# ShiftRegV1_3.net
KiCad netlist of a schematic drawn in EasyEDA
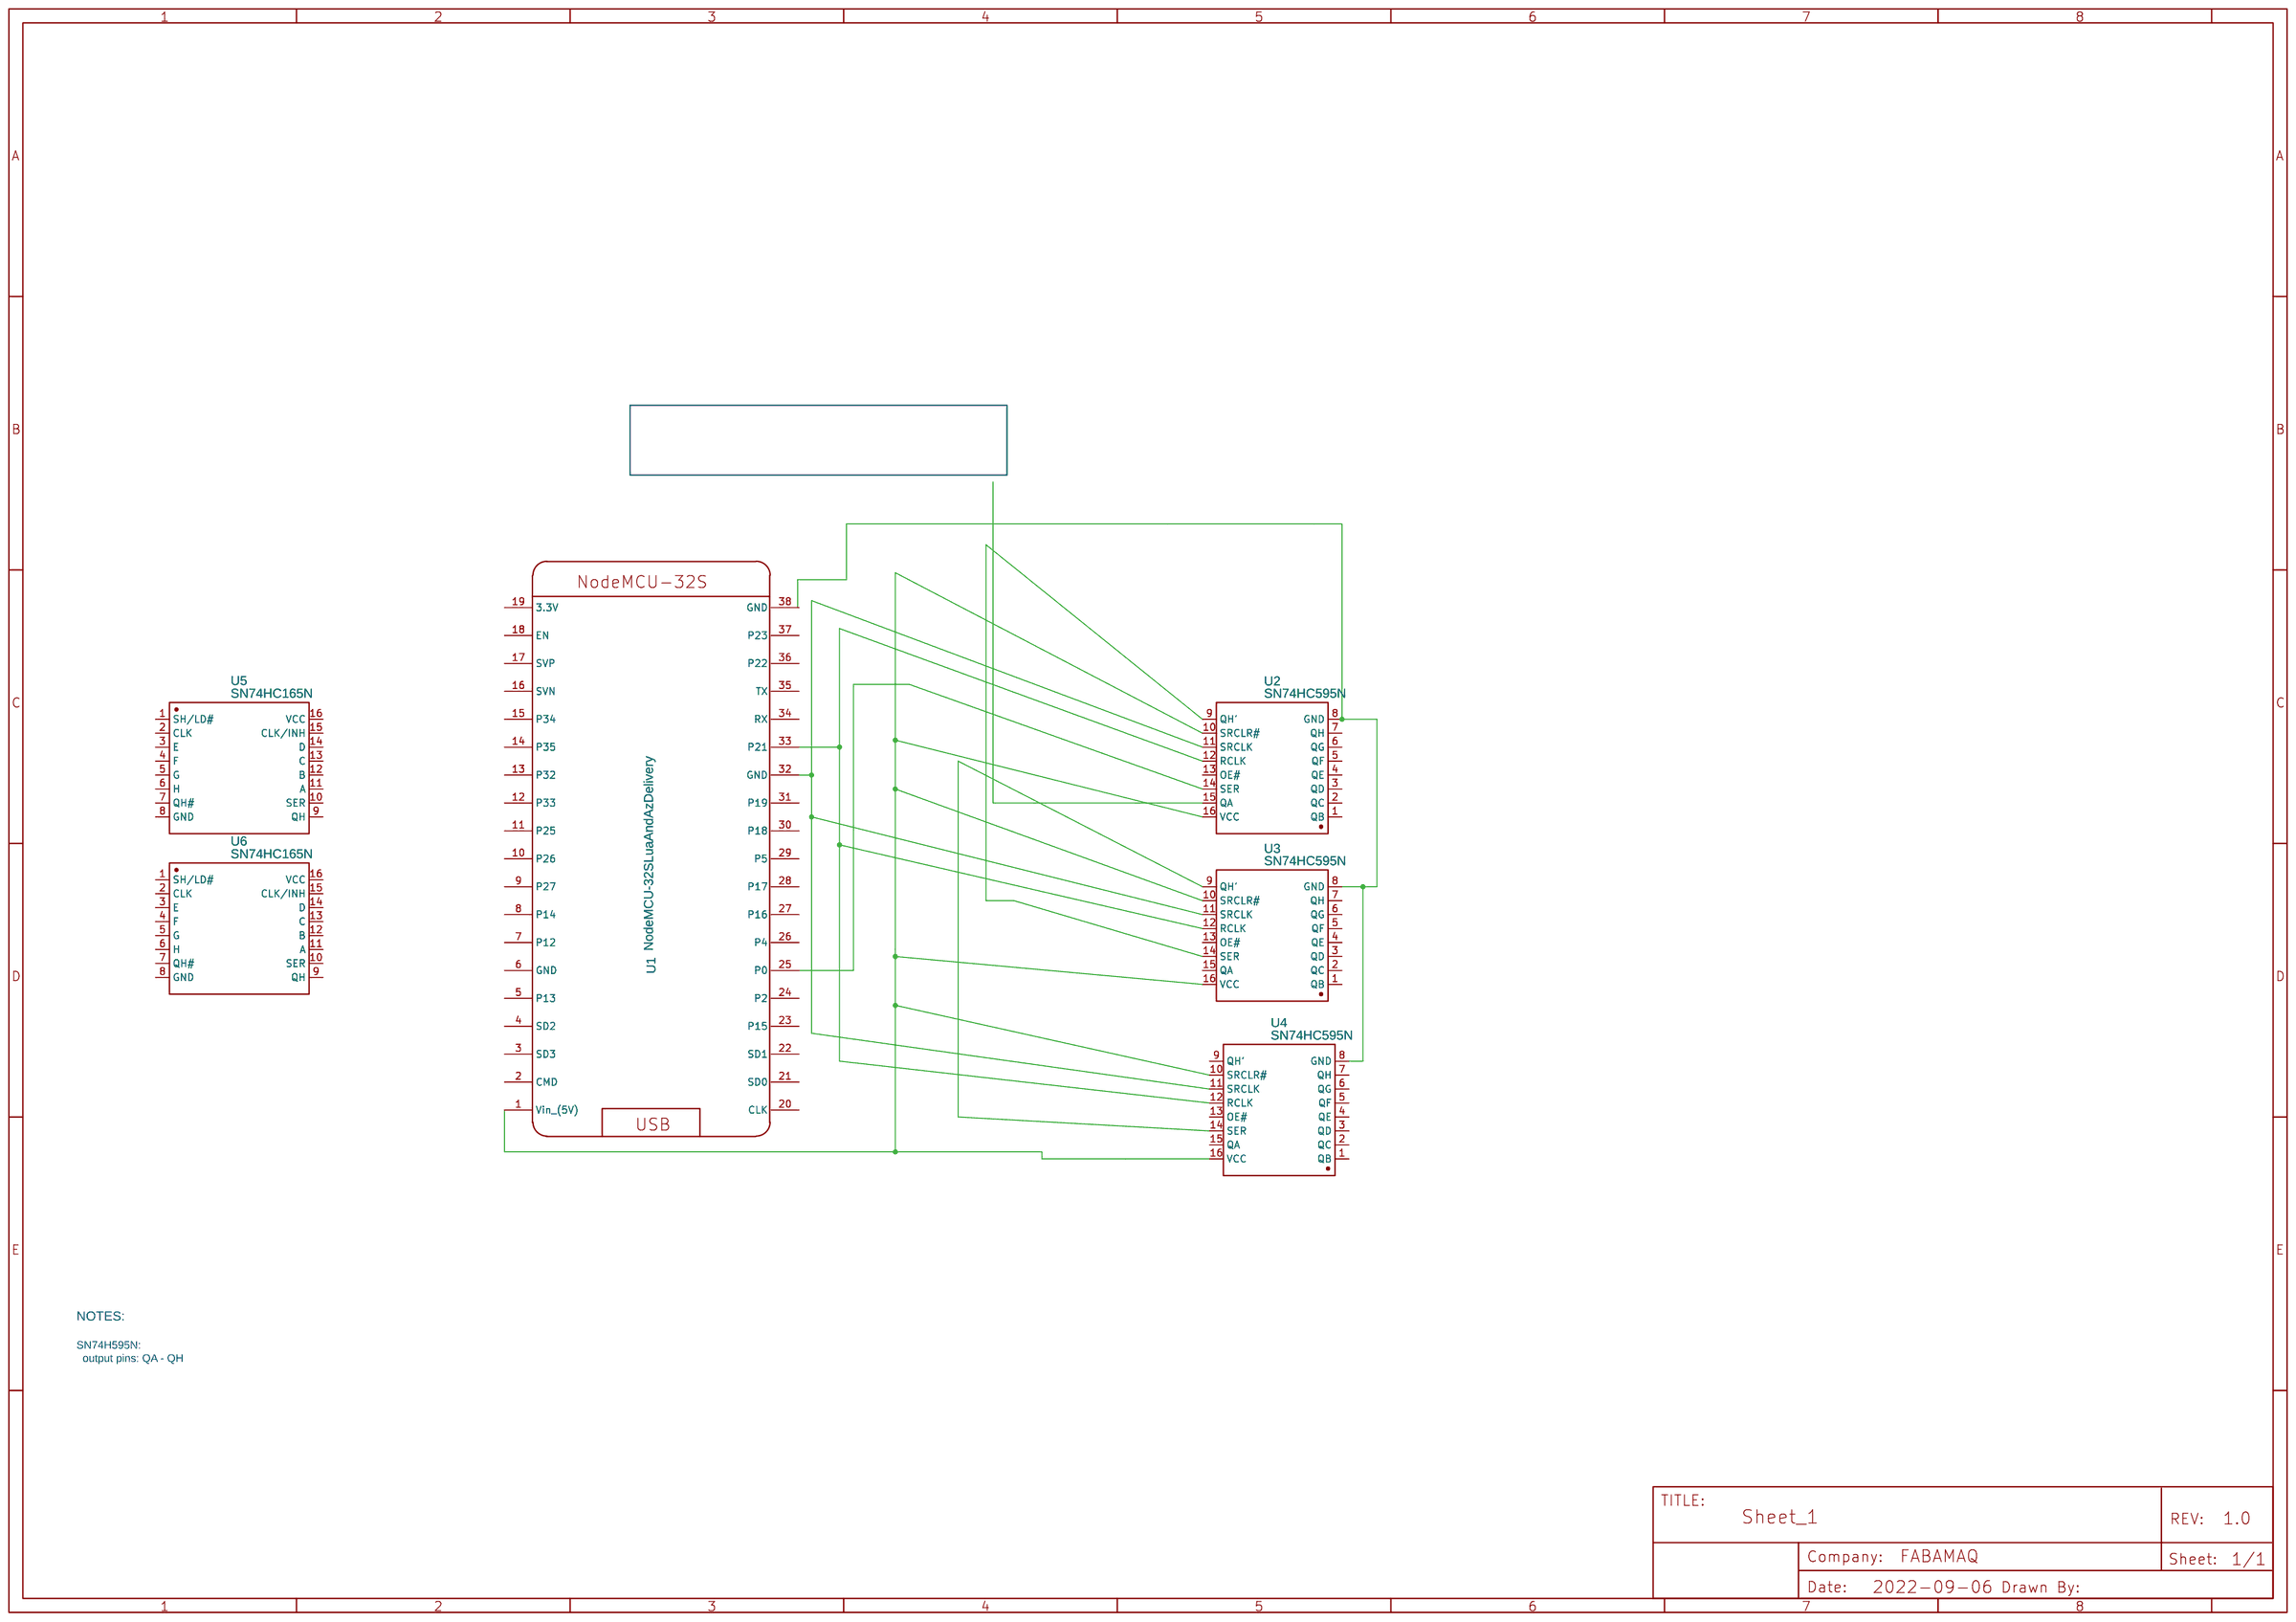
[diagram p0: Sheet_2]
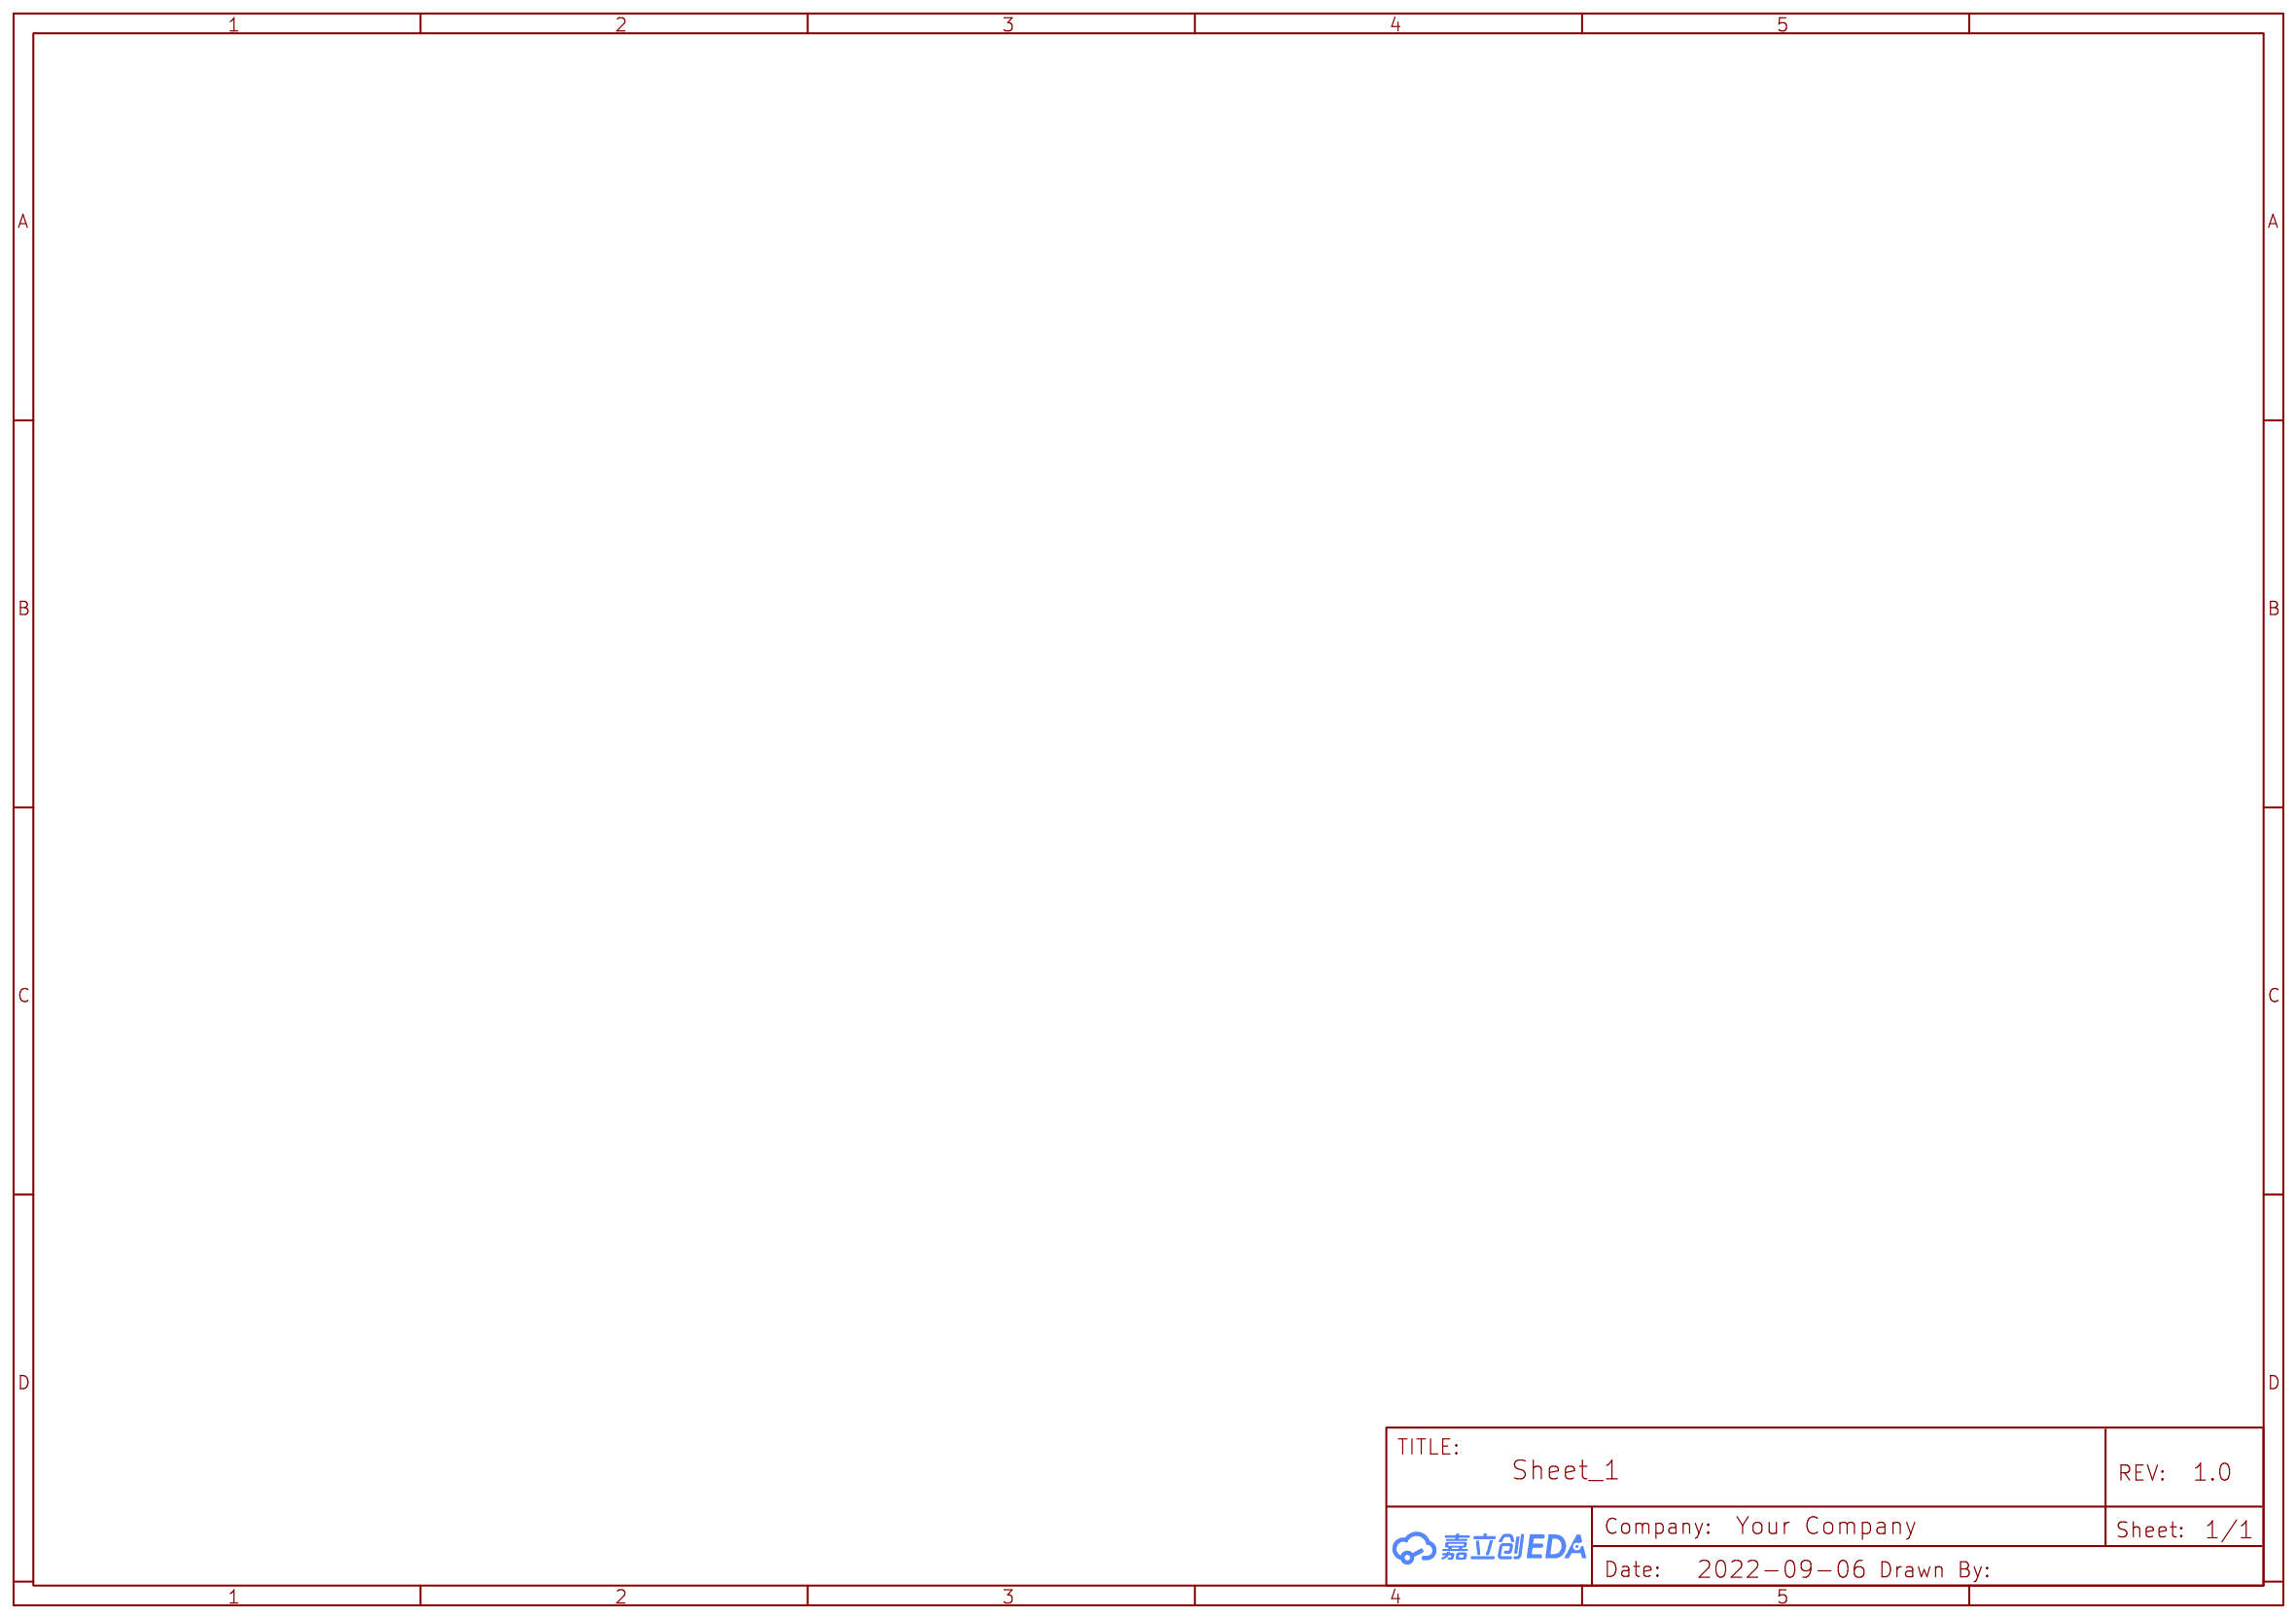
[diagram p1: Sheet_1]

(export (version "E")
  (design (tool "Eeschema 10.0.6"))
  (components
    (comp (ref "U1")
      (value "NodeMCU-32SLuaAndAzDelivery")
      (fields
        (field (name "BOM_Manufacturer Part") "NodeMCU-32SLua")
        (field (name "BOM_Supplier Part") "C111436")
      )
      (libsource (lib "") (part "NodeMCU-32SLuaAndAzDelivery"))
    )
    (comp (ref "U2")
      (value "SN74HC595N")
      (fields (field (name "BOM_Supplier Part") "C78711"))
      (libsource (lib "") (part "SN74HC595N"))
    )
    (comp (ref "U3")
      (value "SN74HC595N")
      (fields (field (name "BOM_Supplier Part") "C78711"))
      (libsource (lib "") (part "SN74HC595N"))
    )
    (comp (ref "U4")
      (value "SN74HC595N")
      (fields (field (name "BOM_Supplier Part") "C78711"))
      (libsource (lib "") (part "SN74HC595N"))
    )
    (comp (ref "U5")
      (value "SN74HC165N")
      (fields (field (name "BOM_Supplier Part") "C2909"))
      (libsource (lib "") (part "SN74HC165N"))
    )
    (comp (ref "U6")
      (value "SN74HC165N")
      (fields (field (name "BOM_Supplier Part") "C2909"))
      (libsource (lib "") (part "SN74HC165N"))
    )
  )
  (nets
    (net (code "1") (name "Net-(U1-P0)") (class "Default")
      (node (ref "U1") (pin "25") (pinfunction "P0_25") (pintype "unspecified"))
      (node (ref "U2") (pin "14") (pinfunction "SER_14") (pintype "unspecified"))
    )
    (net (code "2") (name "Net-(U1-P21)") (class "Default")
      (node (ref "U1") (pin "33") (pinfunction "P21_33") (pintype "unspecified"))
      (node (ref "U2") (pin "12") (pinfunction "RCLK_12") (pintype "unspecified"))
      (node (ref "U3") (pin "12") (pinfunction "RCLK_12") (pintype "unspecified"))
      (node (ref "U4") (pin "12") (pinfunction "RCLK_12") (pintype "unspecified"))
    )
    (net (code "3") (name "Net-(U1-Vin_(5V))") (class "Default")
      (node (ref "U1") (pin "1") (pinfunction "Vin_(5V)_1") (pintype "unspecified"))
      (node (ref "U2") (pin "10") (pinfunction "SRCLR#_10") (pintype "unspecified"))
      (node (ref "U2") (pin "16") (pinfunction "VCC_16") (pintype "unspecified"))
      (node (ref "U3") (pin "10") (pinfunction "SRCLR#_10") (pintype "unspecified"))
      (node (ref "U3") (pin "16") (pinfunction "VCC_16") (pintype "unspecified"))
      (node (ref "U4") (pin "10") (pinfunction "SRCLR#_10") (pintype "unspecified"))
      (node (ref "U4") (pin "16") (pinfunction "VCC_16") (pintype "unspecified"))
    )
    (net (code "4") (name "Net-(U2-GND)") (class "Default")
      (node (ref "U1") (pin "38") (pinfunction "GND_38") (pintype "unspecified"))
      (node (ref "U2") (pin "8") (pinfunction "GND_8") (pintype "unspecified"))
      (node (ref "U3") (pin "8") (pinfunction "GND_8") (pintype "unspecified"))
      (node (ref "U4") (pin "8") (pinfunction "GND_8") (pintype "unspecified"))
    )
    (net (code "5") (name "Net-(U2-QH')") (class "Default")
      (node (ref "U2") (pin "9") (pinfunction "QH'_9") (pintype "unspecified"))
      (node (ref "U3") (pin "14") (pinfunction "SER_14") (pintype "unspecified"))
    )
    (net (code "6") (name "Net-(U2-SRCLK)") (class "Default")
      (node (ref "U1") (pin "32") (pinfunction "GND_32") (pintype "unspecified"))
      (node (ref "U2") (pin "11") (pinfunction "SRCLK_11") (pintype "unspecified"))
      (node (ref "U3") (pin "11") (pinfunction "SRCLK_11") (pintype "unspecified"))
      (node (ref "U4") (pin "11") (pinfunction "SRCLK_11") (pintype "unspecified"))
    )
    (net (code "7") (name "Net-(U3-QH')") (class "Default")
      (node (ref "U3") (pin "9") (pinfunction "QH'_9") (pintype "unspecified"))
      (node (ref "U4") (pin "14") (pinfunction "SER_14") (pintype "unspecified"))
    )
    (net (code "8") (name "unconnected-(U1-3.3V-Pad19)") (class "Default")
      (node (ref "U1") (pin "19") (pinfunction "3.3V_19") (pintype "unspecified"))
    )
    (net (code "9") (name "unconnected-(U1-CLK-Pad20)") (class "Default")
      (node (ref "U1") (pin "20") (pinfunction "CLK_20") (pintype "unspecified"))
    )
    (net (code "10") (name "unconnected-(U1-CMD-Pad2)") (class "Default")
      (node (ref "U1") (pin "2") (pinfunction "CMD_2") (pintype "unspecified"))
    )
    (net (code "11") (name "unconnected-(U1-EN-Pad18)") (class "Default")
      (node (ref "U1") (pin "18") (pinfunction "EN_18") (pintype "unspecified"))
    )
    (net (code "12") (name "unconnected-(U1-GND-Pad6)") (class "Default")
      (node (ref "U1") (pin "6") (pinfunction "GND_6") (pintype "unspecified"))
    )
    (net (code "13") (name "unconnected-(U1-P2-Pad24)") (class "Default")
      (node (ref "U1") (pin "24") (pinfunction "P2_24") (pintype "unspecified"))
    )
    (net (code "14") (name "unconnected-(U1-P4-Pad26)") (class "Default")
      (node (ref "U1") (pin "26") (pinfunction "P4_26") (pintype "unspecified"))
    )
    (net (code "15") (name "unconnected-(U1-P5-Pad29)") (class "Default")
      (node (ref "U1") (pin "29") (pinfunction "P5_29") (pintype "unspecified"))
    )
    (net (code "16") (name "unconnected-(U1-P12-Pad7)") (class "Default")
      (node (ref "U1") (pin "7") (pinfunction "P12_7") (pintype "unspecified"))
    )
    (net (code "17") (name "unconnected-(U1-P13-Pad5)") (class "Default")
      (node (ref "U1") (pin "5") (pinfunction "P13_5") (pintype "unspecified"))
    )
    (net (code "18") (name "unconnected-(U1-P14-Pad8)") (class "Default")
      (node (ref "U1") (pin "8") (pinfunction "P14_8") (pintype "unspecified"))
    )
    (net (code "19") (name "unconnected-(U1-P15-Pad23)") (class "Default")
      (node (ref "U1") (pin "23") (pinfunction "P15_23") (pintype "unspecified"))
    )
    (net (code "20") (name "unconnected-(U1-P16-Pad27)") (class "Default")
      (node (ref "U1") (pin "27") (pinfunction "P16_27") (pintype "unspecified"))
    )
    (net (code "21") (name "unconnected-(U1-P17-Pad28)") (class "Default")
      (node (ref "U1") (pin "28") (pinfunction "P17_28") (pintype "unspecified"))
    )
    (net (code "22") (name "unconnected-(U1-P18-Pad30)") (class "Default")
      (node (ref "U1") (pin "30") (pinfunction "P18_30") (pintype "unspecified"))
    )
    (net (code "23") (name "unconnected-(U1-P19-Pad31)") (class "Default")
      (node (ref "U1") (pin "31") (pinfunction "P19_31") (pintype "unspecified"))
    )
    (net (code "24") (name "unconnected-(U1-P22-Pad36)") (class "Default")
      (node (ref "U1") (pin "36") (pinfunction "P22_36") (pintype "unspecified"))
    )
    (net (code "25") (name "unconnected-(U1-P23-Pad37)") (class "Default")
      (node (ref "U1") (pin "37") (pinfunction "P23_37") (pintype "unspecified"))
    )
    (net (code "26") (name "unconnected-(U1-P25-Pad11)") (class "Default")
      (node (ref "U1") (pin "11") (pinfunction "P25_11") (pintype "unspecified"))
    )
    (net (code "27") (name "unconnected-(U1-P26-Pad10)") (class "Default")
      (node (ref "U1") (pin "10") (pinfunction "P26_10") (pintype "unspecified"))
    )
    (net (code "28") (name "unconnected-(U1-P27-Pad9)") (class "Default")
      (node (ref "U1") (pin "9") (pinfunction "P27_9") (pintype "unspecified"))
    )
    (net (code "29") (name "unconnected-(U1-P32-Pad13)") (class "Default")
      (node (ref "U1") (pin "13") (pinfunction "P32_13") (pintype "unspecified"))
    )
    (net (code "30") (name "unconnected-(U1-P33-Pad12)") (class "Default")
      (node (ref "U1") (pin "12") (pinfunction "P33_12") (pintype "unspecified"))
    )
    (net (code "31") (name "unconnected-(U1-P34-Pad15)") (class "Default")
      (node (ref "U1") (pin "15") (pinfunction "P34_15") (pintype "unspecified"))
    )
    (net (code "32") (name "unconnected-(U1-P35-Pad14)") (class "Default")
      (node (ref "U1") (pin "14") (pinfunction "P35_14") (pintype "unspecified"))
    )
    (net (code "33") (name "unconnected-(U1-RX-Pad34)") (class "Default")
      (node (ref "U1") (pin "34") (pinfunction "RX_34") (pintype "unspecified"))
    )
    (net (code "34") (name "unconnected-(U1-SD0-Pad21)") (class "Default")
      (node (ref "U1") (pin "21") (pinfunction "SD0_21") (pintype "unspecified"))
    )
    (net (code "35") (name "unconnected-(U1-SD1-Pad22)") (class "Default")
      (node (ref "U1") (pin "22") (pinfunction "SD1_22") (pintype "unspecified"))
    )
    (net (code "36") (name "unconnected-(U1-SD2-Pad4)") (class "Default")
      (node (ref "U1") (pin "4") (pinfunction "SD2_4") (pintype "unspecified"))
    )
    (net (code "37") (name "unconnected-(U1-SD3-Pad3)") (class "Default")
      (node (ref "U1") (pin "3") (pinfunction "SD3_3") (pintype "unspecified"))
    )
    (net (code "38") (name "unconnected-(U1-SVN-Pad16)") (class "Default")
      (node (ref "U1") (pin "16") (pinfunction "SVN_16") (pintype "unspecified"))
    )
    (net (code "39") (name "unconnected-(U1-SVP-Pad17)") (class "Default")
      (node (ref "U1") (pin "17") (pinfunction "SVP_17") (pintype "unspecified"))
    )
    (net (code "40") (name "unconnected-(U1-TX-Pad35)") (class "Default")
      (node (ref "U1") (pin "35") (pinfunction "TX_35") (pintype "unspecified"))
    )
    (net (code "41") (name "unconnected-(U2-OE#-Pad13)") (class "Default")
      (node (ref "U2") (pin "13") (pinfunction "OE#_13") (pintype "unspecified"))
    )
    (net (code "42") (name "unconnected-(U2-QA-Pad15)") (class "Default")
      (node (ref "U2") (pin "15") (pinfunction "QA_15") (pintype "unspecified"))
    )
    (net (code "43") (name "unconnected-(U2-QB-Pad1)") (class "Default")
      (node (ref "U2") (pin "1") (pinfunction "QB_1") (pintype "unspecified"))
    )
    (net (code "44") (name "unconnected-(U2-QC-Pad2)") (class "Default")
      (node (ref "U2") (pin "2") (pinfunction "QC_2") (pintype "unspecified"))
    )
    (net (code "45") (name "unconnected-(U2-QD-Pad3)") (class "Default")
      (node (ref "U2") (pin "3") (pinfunction "QD_3") (pintype "unspecified"))
    )
    (net (code "46") (name "unconnected-(U2-QE-Pad4)") (class "Default")
      (node (ref "U2") (pin "4") (pinfunction "QE_4") (pintype "unspecified"))
    )
    (net (code "47") (name "unconnected-(U2-QF-Pad5)") (class "Default")
      (node (ref "U2") (pin "5") (pinfunction "QF_5") (pintype "unspecified"))
    )
    (net (code "48") (name "unconnected-(U2-QG-Pad6)") (class "Default")
      (node (ref "U2") (pin "6") (pinfunction "QG_6") (pintype "unspecified"))
    )
    (net (code "49") (name "unconnected-(U2-QH-Pad7)") (class "Default")
      (node (ref "U2") (pin "7") (pinfunction "QH_7") (pintype "unspecified"))
    )
    (net (code "50") (name "unconnected-(U3-OE#-Pad13)") (class "Default")
      (node (ref "U3") (pin "13") (pinfunction "OE#_13") (pintype "unspecified"))
    )
    (net (code "51") (name "unconnected-(U3-QA-Pad15)") (class "Default")
      (node (ref "U3") (pin "15") (pinfunction "QA_15") (pintype "unspecified"))
    )
    (net (code "52") (name "unconnected-(U3-QB-Pad1)") (class "Default")
      (node (ref "U3") (pin "1") (pinfunction "QB_1") (pintype "unspecified"))
    )
    (net (code "53") (name "unconnected-(U3-QC-Pad2)") (class "Default")
      (node (ref "U3") (pin "2") (pinfunction "QC_2") (pintype "unspecified"))
    )
    (net (code "54") (name "unconnected-(U3-QD-Pad3)") (class "Default")
      (node (ref "U3") (pin "3") (pinfunction "QD_3") (pintype "unspecified"))
    )
    (net (code "55") (name "unconnected-(U3-QE-Pad4)") (class "Default")
      (node (ref "U3") (pin "4") (pinfunction "QE_4") (pintype "unspecified"))
    )
    (net (code "56") (name "unconnected-(U3-QF-Pad5)") (class "Default")
      (node (ref "U3") (pin "5") (pinfunction "QF_5") (pintype "unspecified"))
    )
    (net (code "57") (name "unconnected-(U3-QG-Pad6)") (class "Default")
      (node (ref "U3") (pin "6") (pinfunction "QG_6") (pintype "unspecified"))
    )
    (net (code "58") (name "unconnected-(U3-QH-Pad7)") (class "Default")
      (node (ref "U3") (pin "7") (pinfunction "QH_7") (pintype "unspecified"))
    )
    (net (code "59") (name "unconnected-(U4-OE#-Pad13)") (class "Default")
      (node (ref "U4") (pin "13") (pinfunction "OE#_13") (pintype "unspecified"))
    )
    (net (code "60") (name "unconnected-(U4-QA-Pad15)") (class "Default")
      (node (ref "U4") (pin "15") (pinfunction "QA_15") (pintype "unspecified"))
    )
    (net (code "61") (name "unconnected-(U4-QB-Pad1)") (class "Default")
      (node (ref "U4") (pin "1") (pinfunction "QB_1") (pintype "unspecified"))
    )
    (net (code "62") (name "unconnected-(U4-QC-Pad2)") (class "Default")
      (node (ref "U4") (pin "2") (pinfunction "QC_2") (pintype "unspecified"))
    )
    (net (code "63") (name "unconnected-(U4-QD-Pad3)") (class "Default")
      (node (ref "U4") (pin "3") (pinfunction "QD_3") (pintype "unspecified"))
    )
    (net (code "64") (name "unconnected-(U4-QE-Pad4)") (class "Default")
      (node (ref "U4") (pin "4") (pinfunction "QE_4") (pintype "unspecified"))
    )
    (net (code "65") (name "unconnected-(U4-QF-Pad5)") (class "Default")
      (node (ref "U4") (pin "5") (pinfunction "QF_5") (pintype "unspecified"))
    )
    (net (code "66") (name "unconnected-(U4-QG-Pad6)") (class "Default")
      (node (ref "U4") (pin "6") (pinfunction "QG_6") (pintype "unspecified"))
    )
    (net (code "67") (name "unconnected-(U4-QH'-Pad9)") (class "Default")
      (node (ref "U4") (pin "9") (pinfunction "QH'_9") (pintype "unspecified"))
    )
    (net (code "68") (name "unconnected-(U4-QH-Pad7)") (class "Default")
      (node (ref "U4") (pin "7") (pinfunction "QH_7") (pintype "unspecified"))
    )
    (net (code "69") (name "unconnected-(U5-A-Pad11)") (class "Default")
      (node (ref "U5") (pin "11") (pinfunction "A_11") (pintype "unspecified"))
    )
    (net (code "70") (name "unconnected-(U5-B-Pad12)") (class "Default")
      (node (ref "U5") (pin "12") (pinfunction "B_12") (pintype "unspecified"))
    )
    (net (code "71") (name "unconnected-(U5-C-Pad13)") (class "Default")
      (node (ref "U5") (pin "13") (pinfunction "C_13") (pintype "unspecified"))
    )
    (net (code "72") (name "unconnected-(U5-CLK-Pad2)") (class "Default")
      (node (ref "U5") (pin "2") (pinfunction "CLK_2") (pintype "unspecified"))
    )
    (net (code "73") (name "unconnected-(U5-CLK{slash}INH-Pad15)") (class "Default")
      (node (ref "U5") (pin "15") (pinfunction "CLK/INH_15") (pintype "unspecified"))
    )
    (net (code "74") (name "unconnected-(U5-D-Pad14)") (class "Default")
      (node (ref "U5") (pin "14") (pinfunction "D_14") (pintype "unspecified"))
    )
    (net (code "75") (name "unconnected-(U5-E-Pad3)") (class "Default")
      (node (ref "U5") (pin "3") (pinfunction "E_3") (pintype "unspecified"))
    )
    (net (code "76") (name "unconnected-(U5-F-Pad4)") (class "Default")
      (node (ref "U5") (pin "4") (pinfunction "F_4") (pintype "unspecified"))
    )
    (net (code "77") (name "unconnected-(U5-G-Pad5)") (class "Default")
      (node (ref "U5") (pin "5") (pinfunction "G_5") (pintype "unspecified"))
    )
    (net (code "78") (name "unconnected-(U5-GND-Pad8)") (class "Default")
      (node (ref "U5") (pin "8") (pinfunction "GND_8") (pintype "unspecified"))
    )
    (net (code "79") (name "unconnected-(U5-H-Pad6)") (class "Default")
      (node (ref "U5") (pin "6") (pinfunction "H_6") (pintype "unspecified"))
    )
    (net (code "80") (name "unconnected-(U5-QH#-Pad7)") (class "Default")
      (node (ref "U5") (pin "7") (pinfunction "QH#_7") (pintype "unspecified"))
    )
    (net (code "81") (name "unconnected-(U5-QH-Pad9)") (class "Default")
      (node (ref "U5") (pin "9") (pinfunction "QH_9") (pintype "unspecified"))
    )
    (net (code "82") (name "unconnected-(U5-SER-Pad10)") (class "Default")
      (node (ref "U5") (pin "10") (pinfunction "SER_10") (pintype "unspecified"))
    )
    (net (code "83") (name "unconnected-(U5-SH{slash}LD#-Pad1)") (class "Default")
      (node (ref "U5") (pin "1") (pinfunction "SH/LD#_1") (pintype "unspecified"))
    )
    (net (code "84") (name "unconnected-(U5-VCC-Pad16)") (class "Default")
      (node (ref "U5") (pin "16") (pinfunction "VCC_16") (pintype "unspecified"))
    )
    (net (code "85") (name "unconnected-(U6-A-Pad11)") (class "Default")
      (node (ref "U6") (pin "11") (pinfunction "A_11") (pintype "unspecified"))
    )
    (net (code "86") (name "unconnected-(U6-B-Pad12)") (class "Default")
      (node (ref "U6") (pin "12") (pinfunction "B_12") (pintype "unspecified"))
    )
    (net (code "87") (name "unconnected-(U6-C-Pad13)") (class "Default")
      (node (ref "U6") (pin "13") (pinfunction "C_13") (pintype "unspecified"))
    )
    (net (code "88") (name "unconnected-(U6-CLK-Pad2)") (class "Default")
      (node (ref "U6") (pin "2") (pinfunction "CLK_2") (pintype "unspecified"))
    )
    (net (code "89") (name "unconnected-(U6-CLK{slash}INH-Pad15)") (class "Default")
      (node (ref "U6") (pin "15") (pinfunction "CLK/INH_15") (pintype "unspecified"))
    )
    (net (code "90") (name "unconnected-(U6-D-Pad14)") (class "Default")
      (node (ref "U6") (pin "14") (pinfunction "D_14") (pintype "unspecified"))
    )
    (net (code "91") (name "unconnected-(U6-E-Pad3)") (class "Default")
      (node (ref "U6") (pin "3") (pinfunction "E_3") (pintype "unspecified"))
    )
    (net (code "92") (name "unconnected-(U6-F-Pad4)") (class "Default")
      (node (ref "U6") (pin "4") (pinfunction "F_4") (pintype "unspecified"))
    )
    (net (code "93") (name "unconnected-(U6-G-Pad5)") (class "Default")
      (node (ref "U6") (pin "5") (pinfunction "G_5") (pintype "unspecified"))
    )
    (net (code "94") (name "unconnected-(U6-GND-Pad8)") (class "Default")
      (node (ref "U6") (pin "8") (pinfunction "GND_8") (pintype "unspecified"))
    )
    (net (code "95") (name "unconnected-(U6-H-Pad6)") (class "Default")
      (node (ref "U6") (pin "6") (pinfunction "H_6") (pintype "unspecified"))
    )
    (net (code "96") (name "unconnected-(U6-QH#-Pad7)") (class "Default")
      (node (ref "U6") (pin "7") (pinfunction "QH#_7") (pintype "unspecified"))
    )
    (net (code "97") (name "unconnected-(U6-QH-Pad9)") (class "Default")
      (node (ref "U6") (pin "9") (pinfunction "QH_9") (pintype "unspecified"))
    )
    (net (code "98") (name "unconnected-(U6-SER-Pad10)") (class "Default")
      (node (ref "U6") (pin "10") (pinfunction "SER_10") (pintype "unspecified"))
    )
    (net (code "99") (name "unconnected-(U6-SH{slash}LD#-Pad1)") (class "Default")
      (node (ref "U6") (pin "1") (pinfunction "SH/LD#_1") (pintype "unspecified"))
    )
    (net (code "100") (name "unconnected-(U6-VCC-Pad16)") (class "Default")
      (node (ref "U6") (pin "16") (pinfunction "VCC_16") (pintype "unspecified"))
    )
  )
)
